# DeadHorsePCB_REV-B.net
KiCad netlist of a schematic drawn in EAGLE
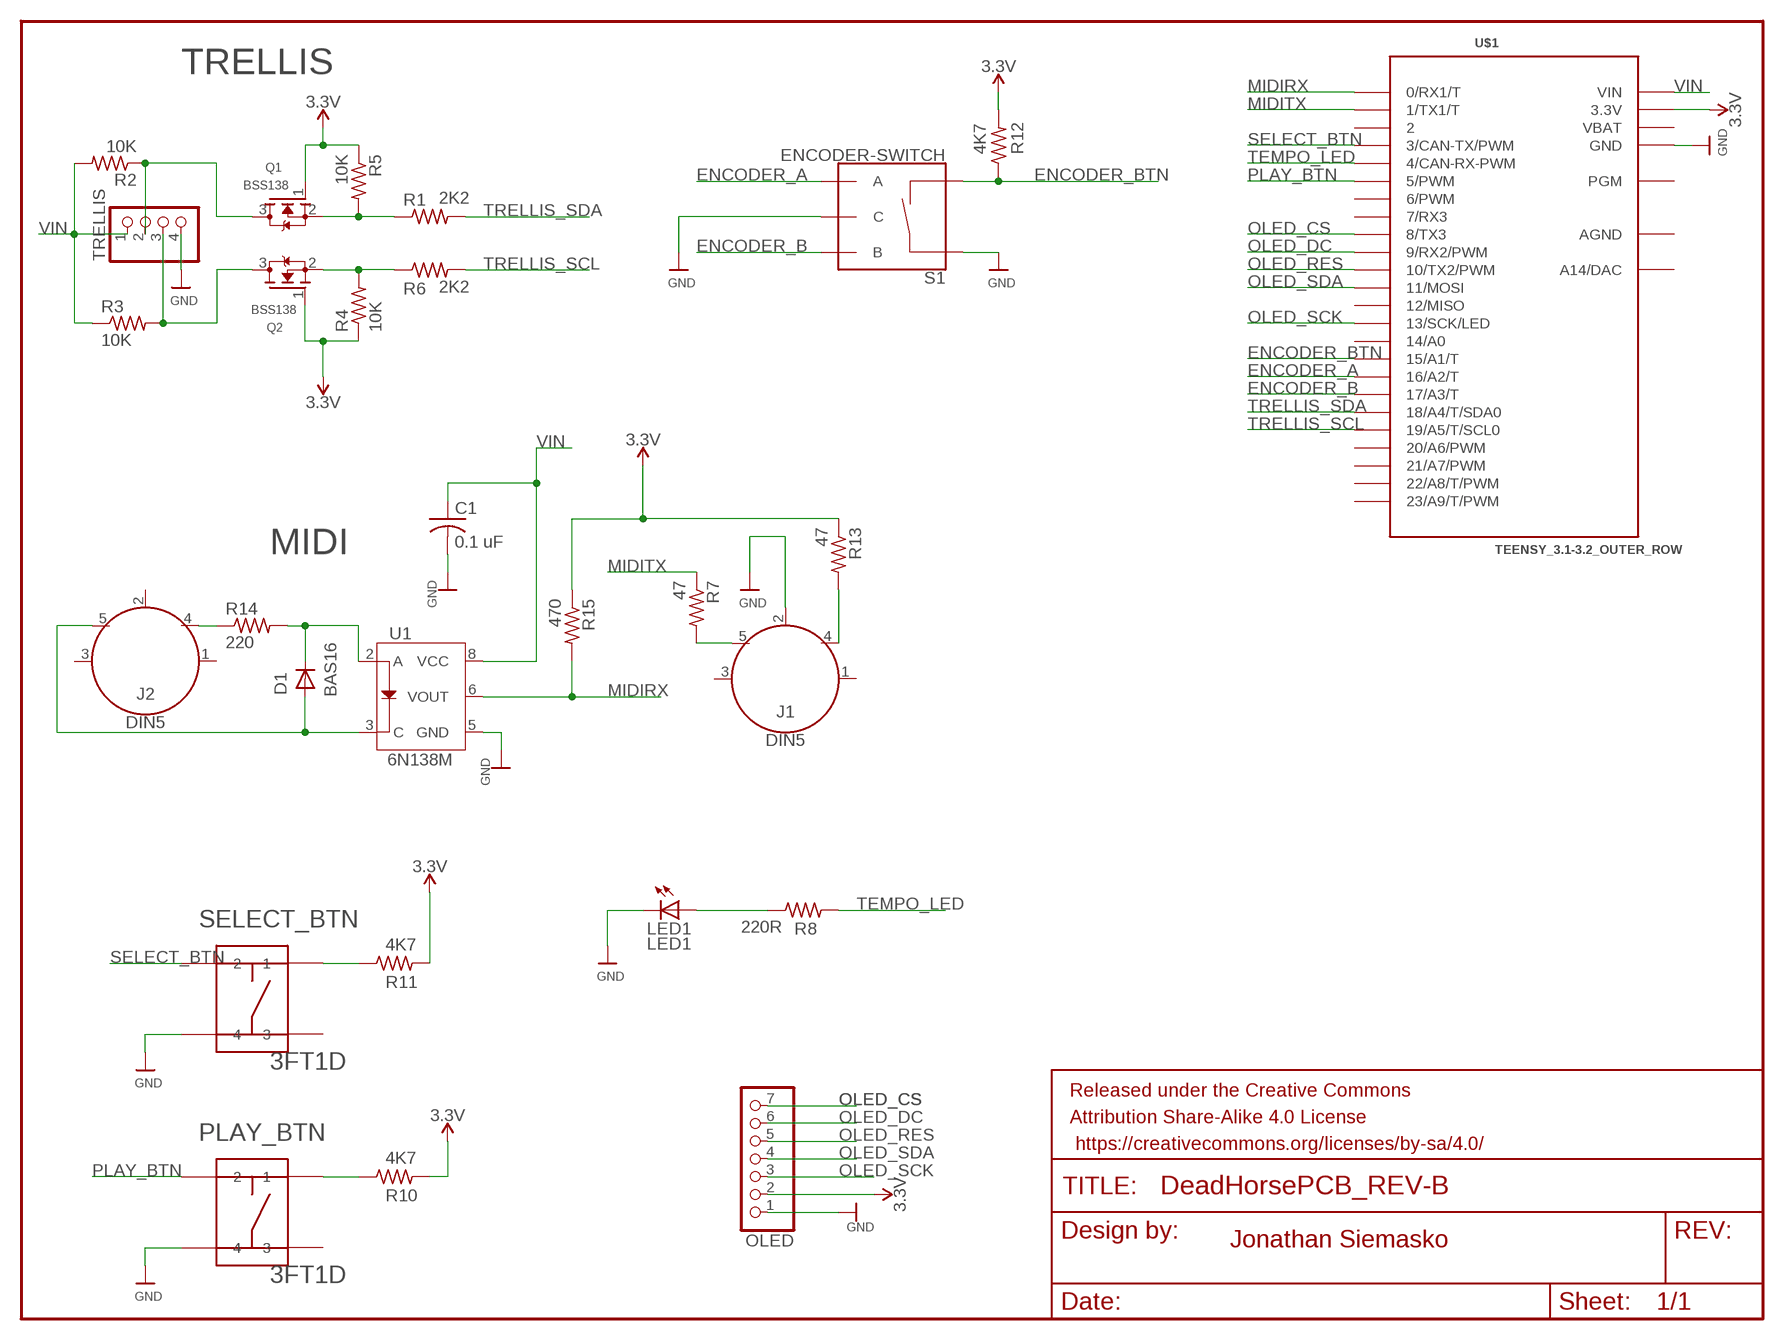
[diagram p0: schematic, sheet 1]

(export (version "E")
  (design (tool "Eeschema 10.0.6"))
  (components
    (comp (ref "C1")
      (value "0.1 uF")
      (footprint "eagle-import:C0805")
      (libsource (lib "eagle-import") (part "C-USC0805"))
    )
    (comp (ref "D1")
      (value "BAS16")
      (footprint "eagle-import:SOT23")
      (libsource (lib "eagle-import") (part "BAS16"))
    )
    (comp (ref "FRAME1")
      (value "FRAME-LETTER")
      (footprint "eagle-import:CREATIVE_COMMONS")
      (libsource (lib "eagle-import") (part "FRAME-LETTER"))
    )
    (comp (ref "J1")
      (value "DIN5")
      (footprint "eagle-import:DIN5-RA-PTH")
      (libsource (lib "eagle-import") (part "DIN5"))
    )
    (comp (ref "J2")
      (value "DIN5")
      (footprint "eagle-import:DIN5-RA-PTH")
      (libsource (lib "eagle-import") (part "DIN5"))
    )
    (comp (ref "LED1")
      (value "LED1")
      (footprint "eagle-import:LED5MM")
      (libsource (lib "eagle-import") (part "LED5MM"))
    )
    (comp (ref "OLED")
      (value "OLED")
      (footprint "eagle-import:1X07")
      (libsource (lib "eagle-import") (part "PINHD-1X7"))
    )
    (comp (ref "PLAY_BTN")
      (value "3FT1D")
      (footprint "eagle-import:3FT")
      (libsource (lib "eagle-import") (part "3FT1D"))
    )
    (comp (ref "Q1")
      (value "BSS138")
      (footprint "eagle-import:SOT23")
      (libsource (lib "eagle-import") (part "MOSFET-NREFLOW"))
    )
    (comp (ref "Q2")
      (value "BSS138")
      (footprint "eagle-import:SOT23")
      (libsource (lib "eagle-import") (part "MOSFET-NREFLOW"))
    )
    (comp (ref "R1")
      (value "2K2")
      (footprint "eagle-import:R0805")
      (libsource (lib "eagle-import") (part "R-US_R0805"))
    )
    (comp (ref "R2")
      (value "10K")
      (footprint "eagle-import:R0805")
      (libsource (lib "eagle-import") (part "R-US_R0805"))
    )
    (comp (ref "R3")
      (value "10K")
      (footprint "eagle-import:R0805")
      (libsource (lib "eagle-import") (part "R-US_R0805"))
    )
    (comp (ref "R4")
      (value "10K")
      (footprint "eagle-import:R0805")
      (libsource (lib "eagle-import") (part "R-US_R0805"))
    )
    (comp (ref "R5")
      (value "10K")
      (footprint "eagle-import:R0805")
      (libsource (lib "eagle-import") (part "R-US_R0805"))
    )
    (comp (ref "R6")
      (value "2K2")
      (footprint "eagle-import:R0805")
      (libsource (lib "eagle-import") (part "R-US_R0805"))
    )
    (comp (ref "R7")
      (value "47")
      (footprint "eagle-import:R0805")
      (libsource (lib "eagle-import") (part "R-US_R0805"))
    )
    (comp (ref "R8")
      (value "220R")
      (footprint "eagle-import:R0805")
      (libsource (lib "eagle-import") (part "R-US_R0805"))
    )
    (comp (ref "R10")
      (value "4K7")
      (footprint "eagle-import:R0805")
      (libsource (lib "eagle-import") (part "R-US_R0805"))
    )
    (comp (ref "R11")
      (value "4K7")
      (footprint "eagle-import:R0805")
      (libsource (lib "eagle-import") (part "R-US_R0805"))
    )
    (comp (ref "R12")
      (value "4K7")
      (footprint "eagle-import:R0805")
      (libsource (lib "eagle-import") (part "R-US_R0805"))
    )
    (comp (ref "R13")
      (value "47")
      (footprint "eagle-import:R0805")
      (libsource (lib "eagle-import") (part "R-US_R0805"))
    )
    (comp (ref "R14")
      (value "220")
      (footprint "eagle-import:R0805")
      (libsource (lib "eagle-import") (part "R-US_R0805"))
    )
    (comp (ref "R15")
      (value "470")
      (footprint "eagle-import:R0805")
      (libsource (lib "eagle-import") (part "R-US_R0805"))
    )
    (comp (ref "S1")
      (value "ENCODER-SWITCH")
      (footprint "eagle-import:ROTARY_ENC_PLAIN")
      (libsource (lib "eagle-import") (part "ENCODER-SWITCH"))
    )
    (comp (ref "SELECT_BTN")
      (value "3FT1D")
      (footprint "eagle-import:3FT")
      (libsource (lib "eagle-import") (part "3FT1D"))
    )
    (comp (ref "TRELLIS")
      (value "TRELLIS")
      (footprint "eagle-import:1X04")
      (libsource (lib "eagle-import") (part "PINHD-1X4"))
    )
    (comp (ref "U$1")
      (value "TEENSY_3.1-3.2_OUTER_ROW")
      (footprint "eagle-import:TEENSY_3.0-3.2&LC_OUTER_ROW")
      (libsource (lib "eagle-import") (part "TEENSY_3.1-3.2_OUTER_ROW"))
    )
    (comp (ref "U1")
      (value "6N138M")
      (footprint "eagle-import:8-SMD")
      (libsource (lib "eagle-import") (part "OPTO_DARL_6N138S"))
    )
  )
  (nets
    (net (code "1") (name "/AGND") (class "Default")
      (node (ref "U$1") (pin "AGND") (pinfunction "AGND_AGND") (pintype "power_in"))
    )
    (net (code "2") (name "/ENCODER_A") (class "Default")
      (node (ref "S1") (pin "A") (pinfunction "A_A") (pintype "bidirectional"))
      (node (ref "U$1") (pin "16/A2") (pinfunction "16/A2/T_16/A2") (pintype "bidirectional"))
    )
    (net (code "3") (name "/ENCODER_B") (class "Default")
      (node (ref "S1") (pin "B") (pinfunction "B_B") (pintype "bidirectional"))
      (node (ref "U$1") (pin "17/A3") (pinfunction "17/A3/T_17/A3") (pintype "bidirectional"))
    )
    (net (code "4") (name "/ENCODER_BTN") (class "Default")
      (node (ref "R12") (pin "1") (pinfunction "1_1") (pintype "passive"))
      (node (ref "S1") (pin "SW-") (pinfunction "SW-_SW-") (pintype "bidirectional"))
      (node (ref "U$1") (pin "15/A1") (pinfunction "15/A1/T_15/A1") (pintype "bidirectional"))
    )
    (net (code "5") (name "/MIDIRX") (class "Default")
      (node (ref "R15") (pin "2") (pinfunction "2_2") (pintype "passive"))
      (node (ref "U$1") (pin "0") (pinfunction "0/RX1/T_0") (pintype "bidirectional"))
      (node (ref "U1") (pin "6") (pinfunction "VOUT_6") (pintype "bidirectional"))
    )
    (net (code "6") (name "/MIDITX") (class "Default")
      (node (ref "R7") (pin "1") (pinfunction "1_1") (pintype "passive"))
      (node (ref "U$1") (pin "1") (pinfunction "1/TX1/T_1") (pintype "bidirectional"))
    )
    (net (code "7") (name "/OLED_CS") (class "Default")
      (node (ref "OLED") (pin "7") (pinfunction "7_7") (pintype "passive"))
      (node (ref "U$1") (pin "8") (pinfunction "8/TX3_8") (pintype "bidirectional"))
    )
    (net (code "8") (name "/OLED_DC") (class "Default")
      (node (ref "OLED") (pin "6") (pinfunction "6_6") (pintype "passive"))
      (node (ref "U$1") (pin "9") (pinfunction "9/RX2/PWM_9") (pintype "bidirectional"))
    )
    (net (code "9") (name "/OLED_RES") (class "Default")
      (node (ref "OLED") (pin "5") (pinfunction "5_5") (pintype "passive"))
      (node (ref "U$1") (pin "10") (pinfunction "10/TX2/PWM_10") (pintype "bidirectional"))
    )
    (net (code "10") (name "/OLED_SCK") (class "Default")
      (node (ref "OLED") (pin "3") (pinfunction "3_3") (pintype "passive"))
      (node (ref "U$1") (pin "13") (pinfunction "13/SCK/LED_13") (pintype "bidirectional"))
    )
    (net (code "11") (name "/OLED_SDA") (class "Default")
      (node (ref "OLED") (pin "4") (pinfunction "4_4") (pintype "passive"))
      (node (ref "U$1") (pin "11") (pinfunction "11/MOSI_11") (pintype "bidirectional"))
    )
    (net (code "12") (name "/PLAY_BTN") (class "Default")
      (node (ref "PLAY_BTN") (pin "P$2") (pinfunction "2_P$2") (pintype "bidirectional"))
      (node (ref "U$1") (pin "5") (pinfunction "5/PWM_5") (pintype "bidirectional"))
    )
    (net (code "13") (name "/SELECT_BTN") (class "Default")
      (node (ref "SELECT_BTN") (pin "P$2") (pinfunction "2_P$2") (pintype "bidirectional"))
      (node (ref "U$1") (pin "3") (pinfunction "3/CAN-TX/PWM_3") (pintype "bidirectional"))
    )
    (net (code "14") (name "/TEMPO_LED") (class "Default")
      (node (ref "R8") (pin "2") (pinfunction "2_2") (pintype "passive"))
      (node (ref "U$1") (pin "4") (pinfunction "4/CAN-RX-PWM_4") (pintype "bidirectional"))
    )
    (net (code "15") (name "/TRELLIS_SCL") (class "Default")
      (node (ref "R6") (pin "2") (pinfunction "2_2") (pintype "passive"))
      (node (ref "U$1") (pin "19/A5") (pinfunction "19/A5/T/SCL0_19/A5") (pintype "bidirectional"))
    )
    (net (code "16") (name "/TRELLIS_SDA") (class "Default")
      (node (ref "R1") (pin "2") (pinfunction "2_2") (pintype "passive"))
      (node (ref "U$1") (pin "18/A4") (pinfunction "18/A4/T/SDA0_18/A4") (pintype "bidirectional"))
    )
    (net (code "17") (name "/VBAT") (class "Default")
      (node (ref "U$1") (pin "VBAT") (pinfunction "VBAT_VBAT") (pintype "power_in"))
    )
    (net (code "18") (name "/VIN") (class "Default")
      (node (ref "C1") (pin "1") (pinfunction "1_1") (pintype "passive"))
      (node (ref "R2") (pin "2") (pinfunction "2_2") (pintype "passive"))
      (node (ref "R3") (pin "1") (pinfunction "1_1") (pintype "passive"))
      (node (ref "TRELLIS") (pin "1") (pinfunction "1_1") (pintype "passive"))
      (node (ref "U$1") (pin "VIN") (pinfunction "VIN_VIN") (pintype "power_in"))
      (node (ref "U1") (pin "8") (pinfunction "VCC_8") (pintype "bidirectional"))
    )
    (net (code "19") (name "3.3V") (class "Default")
      (node (ref "OLED") (pin "2") (pinfunction "2_2") (pintype "passive"))
      (node (ref "Q1") (pin "1") (pinfunction "G_1") (pintype "bidirectional"))
      (node (ref "Q2") (pin "1") (pinfunction "G_1") (pintype "bidirectional"))
      (node (ref "R10") (pin "2") (pinfunction "2_2") (pintype "passive"))
      (node (ref "R11") (pin "2") (pinfunction "2_2") (pintype "passive"))
      (node (ref "R12") (pin "2") (pinfunction "2_2") (pintype "passive"))
      (node (ref "R13") (pin "1") (pinfunction "1_1") (pintype "passive"))
      (node (ref "R15") (pin "1") (pinfunction "1_1") (pintype "passive"))
      (node (ref "R4") (pin "1") (pinfunction "1_1") (pintype "passive"))
      (node (ref "R5") (pin "1") (pinfunction "1_1") (pintype "passive"))
      (node (ref "U$1") (pin "3.3V") (pinfunction "3.3V_3.3V") (pintype "power_in"))
      (node (ref "U$1") (pin "3.3V1") (pinfunction "3.3V_3.3V1") (pintype "power_in"))
    )
    (net (code "20") (name "GND") (class "Default")
      (node (ref "C1") (pin "2") (pinfunction "2_2") (pintype "passive"))
      (node (ref "J1") (pin "2") (pinfunction "2_2") (pintype "bidirectional"))
      (node (ref "LED1") (pin "K") (pinfunction "C_K") (pintype "passive"))
      (node (ref "OLED") (pin "1") (pinfunction "1_1") (pintype "passive"))
      (node (ref "PLAY_BTN") (pin "P$4") (pinfunction "4_P$4") (pintype "bidirectional"))
      (node (ref "S1") (pin "C") (pinfunction "C_C") (pintype "bidirectional"))
      (node (ref "S1") (pin "SW+") (pinfunction "SW+_SW+") (pintype "bidirectional"))
      (node (ref "SELECT_BTN") (pin "P$4") (pinfunction "4_P$4") (pintype "bidirectional"))
      (node (ref "TRELLIS") (pin "4") (pinfunction "4_4") (pintype "passive"))
      (node (ref "U$1") (pin "GND") (pinfunction "GND_GND") (pintype "power_in"))
      (node (ref "U$1") (pin "GND1") (pinfunction "GND_GND1") (pintype "power_in"))
      (node (ref "U1") (pin "5") (pinfunction "GND_5") (pintype "bidirectional"))
    )
    (net (code "21") (name "Net-(D1-A)") (class "Default")
      (node (ref "D1") (pin "1") (pinfunction "A_1") (pintype "passive"))
      (node (ref "J2") (pin "5") (pinfunction "5_5") (pintype "bidirectional"))
      (node (ref "U1") (pin "3") (pinfunction "C_3") (pintype "bidirectional"))
    )
    (net (code "22") (name "Net-(D1-K)") (class "Default")
      (node (ref "D1") (pin "3") (pinfunction "K_3") (pintype "passive"))
      (node (ref "R14") (pin "2") (pinfunction "2_2") (pintype "passive"))
      (node (ref "U1") (pin "2") (pinfunction "A_2") (pintype "bidirectional"))
    )
    (net (code "23") (name "Net-(J1-Pad4)") (class "Default")
      (node (ref "J1") (pin "4") (pinfunction "4_4") (pintype "bidirectional"))
      (node (ref "R13") (pin "2") (pinfunction "2_2") (pintype "passive"))
    )
    (net (code "24") (name "Net-(J1-Pad5)") (class "Default")
      (node (ref "J1") (pin "5") (pinfunction "5_5") (pintype "bidirectional"))
      (node (ref "R7") (pin "2") (pinfunction "2_2") (pintype "passive"))
    )
    (net (code "25") (name "Net-(J2-Pad4)") (class "Default")
      (node (ref "J2") (pin "4") (pinfunction "4_4") (pintype "bidirectional"))
      (node (ref "R14") (pin "1") (pinfunction "1_1") (pintype "passive"))
    )
    (net (code "26") (name "Net-(LED1-PadA)") (class "Default")
      (node (ref "LED1") (pin "A") (pinfunction "A_A") (pintype "passive"))
      (node (ref "R8") (pin "1") (pinfunction "1_1") (pintype "passive"))
    )
    (net (code "27") (name "Net-(PLAY_BTN-1)") (class "Default")
      (node (ref "PLAY_BTN") (pin "P$1") (pinfunction "1_P$1") (pintype "bidirectional"))
      (node (ref "R10") (pin "1") (pinfunction "1_1") (pintype "passive"))
    )
    (net (code "28") (name "Net-(Q1-D)") (class "Default")
      (node (ref "Q1") (pin "3") (pinfunction "D_3") (pintype "bidirectional"))
      (node (ref "R2") (pin "1") (pinfunction "1_1") (pintype "passive"))
      (node (ref "TRELLIS") (pin "2") (pinfunction "2_2") (pintype "passive"))
    )
    (net (code "29") (name "Net-(Q1-S)") (class "Default")
      (node (ref "Q1") (pin "2") (pinfunction "S_2") (pintype "bidirectional"))
      (node (ref "R1") (pin "1") (pinfunction "1_1") (pintype "passive"))
      (node (ref "R5") (pin "2") (pinfunction "2_2") (pintype "passive"))
    )
    (net (code "30") (name "Net-(Q2-D)") (class "Default")
      (node (ref "Q2") (pin "3") (pinfunction "D_3") (pintype "bidirectional"))
      (node (ref "R3") (pin "2") (pinfunction "2_2") (pintype "passive"))
      (node (ref "TRELLIS") (pin "3") (pinfunction "3_3") (pintype "passive"))
    )
    (net (code "31") (name "Net-(Q2-S)") (class "Default")
      (node (ref "Q2") (pin "2") (pinfunction "S_2") (pintype "bidirectional"))
      (node (ref "R4") (pin "2") (pinfunction "2_2") (pintype "passive"))
      (node (ref "R6") (pin "1") (pinfunction "1_1") (pintype "passive"))
    )
    (net (code "32") (name "Net-(SELECT_BTN-1)") (class "Default")
      (node (ref "R11") (pin "1") (pinfunction "1_1") (pintype "passive"))
      (node (ref "SELECT_BTN") (pin "P$1") (pinfunction "1_P$1") (pintype "bidirectional"))
    )
    (net (code "33") (name "unconnected-(J1-Pad1)") (class "Default")
      (node (ref "J1") (pin "1") (pinfunction "1_1") (pintype "bidirectional"))
    )
    (net (code "34") (name "unconnected-(J1-Pad3)") (class "Default")
      (node (ref "J1") (pin "3") (pinfunction "3_3") (pintype "bidirectional"))
    )
    (net (code "35") (name "unconnected-(J2-Pad1)") (class "Default")
      (node (ref "J2") (pin "1") (pinfunction "1_1") (pintype "bidirectional"))
    )
    (net (code "36") (name "unconnected-(J2-Pad2)") (class "Default")
      (node (ref "J2") (pin "2") (pinfunction "2_2") (pintype "bidirectional"))
    )
    (net (code "37") (name "unconnected-(J2-Pad3)") (class "Default")
      (node (ref "J2") (pin "3") (pinfunction "3_3") (pintype "bidirectional"))
    )
    (net (code "38") (name "unconnected-(PLAY_BTN-3-PadP$3)") (class "Default")
      (node (ref "PLAY_BTN") (pin "P$3") (pinfunction "3_P$3") (pintype "bidirectional"))
    )
    (net (code "39") (name "unconnected-(SELECT_BTN-3-PadP$3)") (class "Default")
      (node (ref "SELECT_BTN") (pin "P$3") (pinfunction "3_P$3") (pintype "bidirectional"))
    )
    (net (code "40") (name "unconnected-(U$1-6{slash}PWM-Pad6)") (class "Default")
      (node (ref "U$1") (pin "6") (pinfunction "6/PWM_6") (pintype "bidirectional"))
    )
    (net (code "41") (name "unconnected-(U$1-7{slash}RX3-Pad7)") (class "Default")
      (node (ref "U$1") (pin "7") (pinfunction "7/RX3_7") (pintype "bidirectional"))
    )
    (net (code "42") (name "unconnected-(U$1-12{slash}MISO-Pad12)") (class "Default")
      (node (ref "U$1") (pin "12") (pinfunction "12/MISO_12") (pintype "bidirectional"))
    )
    (net (code "43") (name "unconnected-(U$1-20{slash}A6{slash}PWM-Pad20{slash}A6)") (class "Default")
      (node (ref "U$1") (pin "20/A6") (pinfunction "20/A6/PWM_20/A6") (pintype "bidirectional"))
    )
    (net (code "44") (name "unconnected-(U$1-21{slash}A7{slash}PWM-Pad21{slash}A7)") (class "Default")
      (node (ref "U$1") (pin "21/A7") (pinfunction "21/A7/PWM_21/A7") (pintype "bidirectional"))
    )
    (net (code "45") (name "unconnected-(U$1-22{slash}A8{slash}T{slash}PWM-Pad22{slash}A8)") (class "Default")
      (node (ref "U$1") (pin "22/A8") (pinfunction "22/A8/T/PWM_22/A8") (pintype "bidirectional"))
    )
    (net (code "46") (name "unconnected-(U$1-23{slash}A9{slash}T{slash}PWM-Pad23{slash}A9)") (class "Default")
      (node (ref "U$1") (pin "23/A9") (pinfunction "23/A9/T/PWM_23/A9") (pintype "bidirectional"))
    )
    (net (code "47") (name "unconnected-(U$1-A14{slash}DAC-PadRESET{slash}DAC)") (class "Default")
      (node (ref "U$1") (pin "RESET/DAC") (pinfunction "A14/DAC_RESET/DAC") (pintype "bidirectional"))
    )
    (net (code "48") (name "unconnected-(U$1-Pad2)") (class "Default")
      (node (ref "U$1") (pin "2") (pinfunction "2_2") (pintype "bidirectional"))
    )
    (net (code "49") (name "unconnected-(U$1-Pad14{slash}A0)") (class "Default")
      (node (ref "U$1") (pin "14/A0") (pinfunction "14/A0_14/A0") (pintype "bidirectional"))
    )
    (net (code "50") (name "unconnected-(U$1-PadPGM)") (class "Default")
      (node (ref "U$1") (pin "PGM") (pinfunction "PGM_PGM") (pintype "bidirectional"))
    )
  )
)
